# Sch_khech_dai_musis.net
KiCad netlist of a schematic drawn in Altium Designer
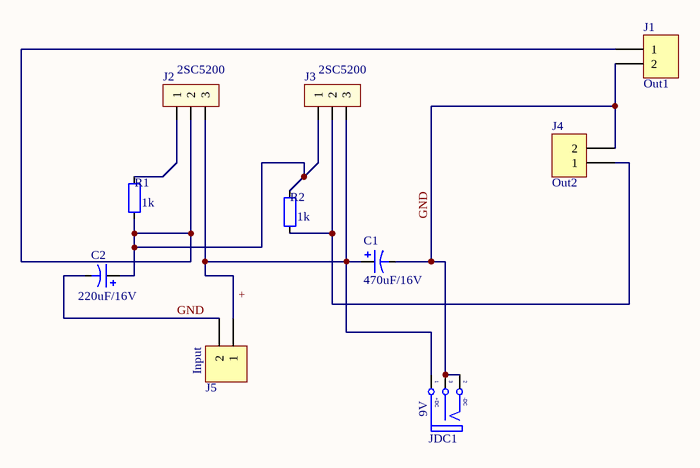
[diagram p0: Sch_khech_dai_musis.SchDoc]

(export (version "E")
  (design (tool "Eeschema 10.0.6"))
  (components
    (comp (ref "C1")
      (value "470uF/16V")
      (footprint "C3MM")
      (description "Polarized Capacitor (Axial)")
      (fields (field (name "PUBLISHER") "Altium Limited"))
      (libsource (lib "My Library_v2") (part "Cap Pol"))
    )
    (comp (ref "C2")
      (value "220uF/16V")
      (footprint "C3MM")
      (description "Polarized Capacitor (Axial)")
      (fields (field (name "PUBLISHER") "Altium Limited"))
      (libsource (lib "My Library_v2") (part "Cap Pol"))
    )
    (comp (ref "J1")
      (value "Out1")
      (footprint "KF2-3.5")
      (fields
        (field (name "MANUFACTURER") "Würth Elektronik eiSos GmbH")
        (field (name "PARTNO") "691103110002")
        (field (name "CREATED BY") "Karrer Zheng")
      )
      (libsource (lib "") (part "KF2_2"))
    )
    (comp (ref "J2")
      (value "2SC5200")
      (footprint "JP3-C1T")
      (description "Jumper 3")
      (libsource (lib "My Library_v2") (part "JP3"))
    )
    (comp (ref "J3")
      (value "2SC5200")
      (footprint "JP3-C1T")
      (description "Jumper 3")
      (libsource (lib "My Library_v2") (part "JP3"))
    )
    (comp (ref "J4")
      (value "Out2")
      (footprint "KF2-3.5")
      (fields
        (field (name "MANUFACTURER") "Würth Elektronik eiSos GmbH")
        (field (name "PARTNO") "691103110002")
        (field (name "CREATED BY") "Karrer Zheng")
      )
      (libsource (lib "My Library_v2") (part "KF2"))
    )
    (comp (ref "J5")
      (value "Input")
      (footprint "KF2-3.5")
      (fields
        (field (name "MANUFACTURER") "Würth Elektronik eiSos GmbH")
        (field (name "PARTNO") "691103110002")
        (field (name "CREATED BY") "Karrer Zheng")
      )
      (libsource (lib "") (part "KF2_1"))
    )
    (comp (ref "JDC1")
      (value "9V")
      (footprint "DC-IN")
      (description "Jac DC input")
      (libsource (lib "My Library_v2") (part "DCIN"))
    )
    (comp (ref "R1")
      (value "1k")
      (footprint "RES-SMD-0805")
      (description "Resistor")
      (fields
        (field (name "MANUFACTURER") "Generic Components")
        (field (name "PUBLISHER") "Altium Hobart Technology Centre")
      )
      (libsource (lib "My Library_v2") (part "Resistor - SMD"))
    )
    (comp (ref "R2")
      (value "1k")
      (footprint "RES-SMD-0805")
      (description "Resistor")
      (fields
        (field (name "MANUFACTURER") "Generic Components")
        (field (name "PUBLISHER") "Altium Hobart Technology Centre")
      )
      (libsource (lib "My Library_v2") (part "Resistor - SMD"))
    )
  )
  (nets
    (net (code "1") (name "/+") (class "Default")
      (node (ref "C1") (pin "1") (pinfunction "1_1") (pintype "passive"))
      (node (ref "J2") (pin "3") (pinfunction "3_3") (pintype "passive"))
      (node (ref "J3") (pin "3") (pinfunction "3_3") (pintype "passive"))
      (node (ref "J5") (pin "1") (pinfunction "1_1") (pintype "passive"))
      (node (ref "JDC1") (pin "1") (pinfunction "T_1") (pintype "passive"))
    )
    (net (code "2") (name "/GND") (class "Default")
      (node (ref "C1") (pin "2") (pinfunction "2_2") (pintype "passive"))
      (node (ref "C2") (pin "2") (pinfunction "2_2") (pintype "passive"))
      (node (ref "J1") (pin "2") (pinfunction "2_2") (pintype "passive"))
      (node (ref "J4") (pin "2") (pinfunction "2_2") (pintype "passive"))
      (node (ref "J5") (pin "2") (pinfunction "2_2") (pintype "passive"))
      (node (ref "JDC1") (pin "2") (pinfunction "TN_2") (pintype "passive"))
      (node (ref "JDC1") (pin "3") (pinfunction "S_3") (pintype "power_in"))
    )
    (net (code "3") (name "Net-(C2-Pad1)") (class "Default")
      (node (ref "C2") (pin "1") (pinfunction "1_1") (pintype "passive"))
      (node (ref "J1") (pin "1") (pinfunction "1_1") (pintype "passive"))
      (node (ref "J2") (pin "2") (pinfunction "2_2") (pintype "passive"))
      (node (ref "J3") (pin "1") (pinfunction "1_1") (pintype "passive"))
      (node (ref "R1") (pin "1") (pinfunction "1_1") (pintype "passive"))
      (node (ref "R2") (pin "2") (pinfunction "2_2") (pintype "passive"))
    )
    (net (code "4") (name "Net-(J2-Pad1)") (class "Default")
      (node (ref "J2") (pin "1") (pinfunction "1_1") (pintype "passive"))
      (node (ref "R1") (pin "2") (pinfunction "2_2") (pintype "passive"))
    )
    (net (code "5") (name "Net-(J3-Pad2)") (class "Default")
      (node (ref "J3") (pin "2") (pinfunction "2_2") (pintype "passive"))
      (node (ref "J4") (pin "1") (pinfunction "1_1") (pintype "passive"))
      (node (ref "R2") (pin "1") (pinfunction "1_1") (pintype "passive"))
    )
  )
)
